# EncoderArm.net
KiCad netlist of a schematic drawn in Altium Designer
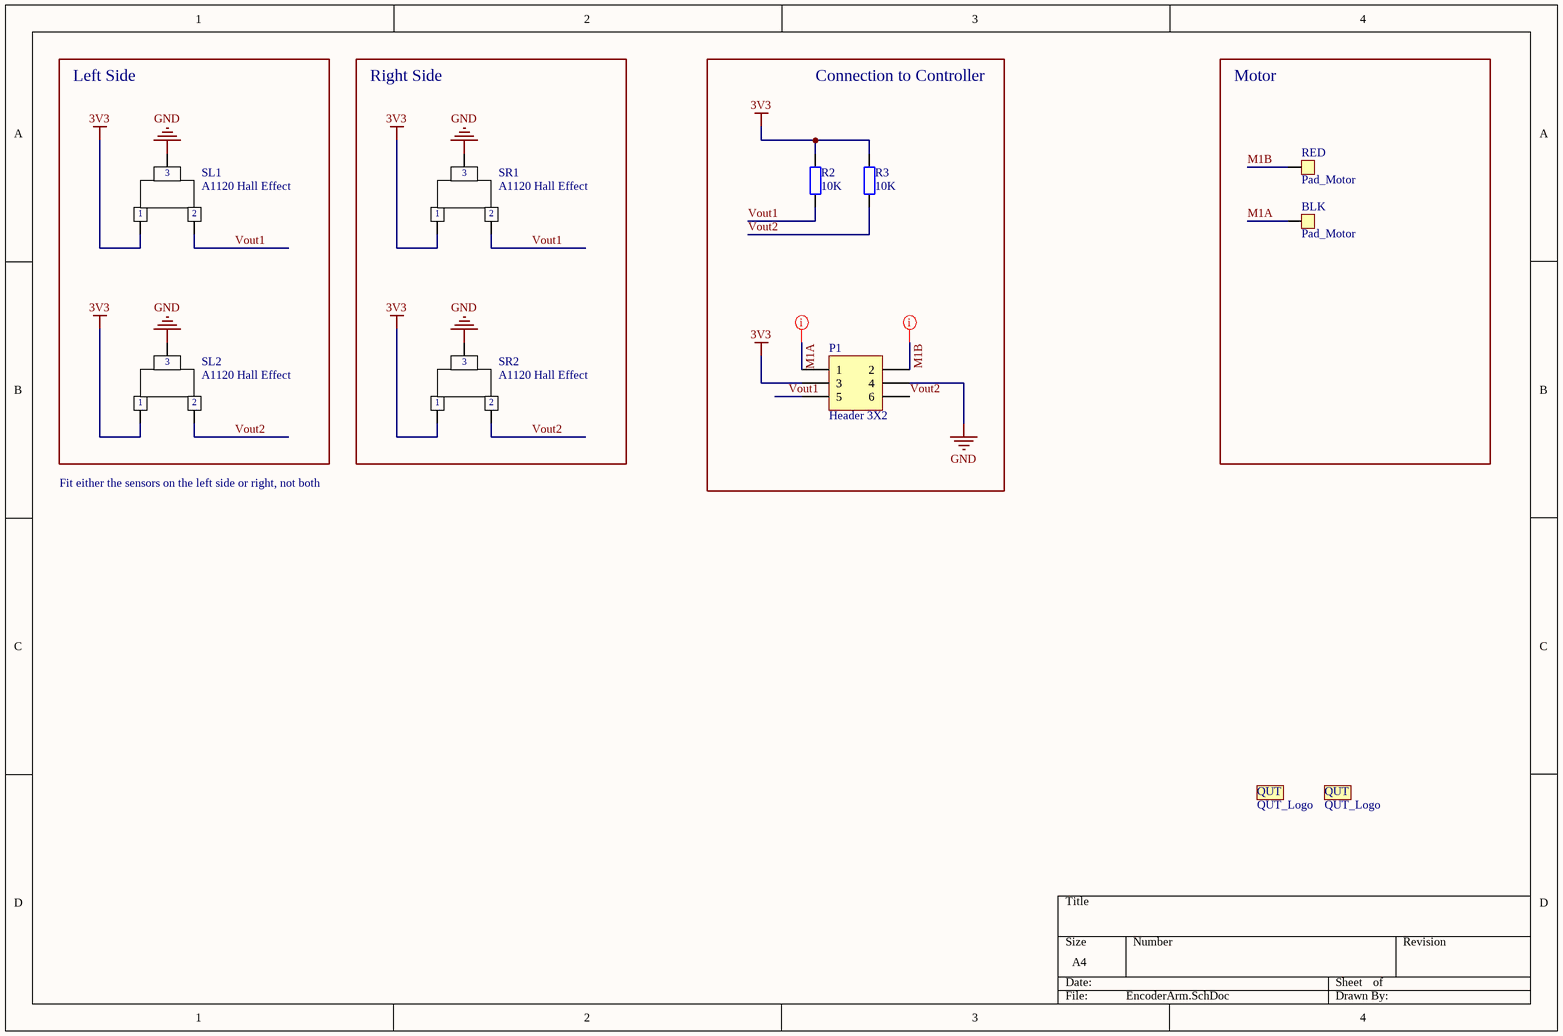
[diagram p0: EncoderArm.SchDoc]

(export (version "E")
  (design (tool "Eeschema 10.0.6"))
  (components
    (comp (ref "BLK")
      (value "Pad_Motor")
      (footprint "Pads_Motor")
      (libsource (lib "PenguinPi_v2") (part "Pad_Motor"))
    )
    (comp (ref "LG1") (value "QUT_Logo") (footprint "QUT_Logo") (libsource (lib "Penguin") (part "QUT_Logo")))
    (comp (ref "LG2") (value "QUT_Logo") (footprint "QUT_Logo") (libsource (lib "Penguin") (part "QUT_Logo")))
    (comp (ref "P1")
      (value "Header 3X2")
      (footprint "HDR2X3")
      (description "Header, 3-Pin, Dual row")
      (fields (field (name "PUBLISHER") "Altium Limited"))
      (libsource (lib "Miscellaneous Connectors") (part "Header 3X2"))
    )
    (comp (ref "R2")
      (value "10K")
      (footprint "6-0805_M")
      (description "Resistor")
      (fields (field (name "Comment") "Res2") (field (name "PUBLISHER") "Altium Limited"))
      (libsource (lib "Miscellaneous Devices") (part "Res2"))
    )
    (comp (ref "R3")
      (value "10K")
      (footprint "6-0805_M")
      (description "Resistor")
      (fields (field (name "Comment") "Res2") (field (name "PUBLISHER") "Altium Limited"))
      (libsource (lib "Miscellaneous Devices") (part "Res2"))
    )
    (comp (ref "RED")
      (value "Pad_Motor")
      (footprint "Pads_Motor")
      (libsource (lib "PenguinPi_v2") (part "Pad_Motor"))
    )
    (comp (ref "SL1")
      (value "A1120 Hall Effect")
      (footprint "SOT23-3N")
      (libsource (lib "QUT") (part "FT_SOT23-3"))
    )
    (comp (ref "SL2")
      (value "A1120 Hall Effect")
      (footprint "SOT23-3N")
      (libsource (lib "QUT") (part "FT_SOT23-3"))
    )
    (comp (ref "SR1")
      (value "A1120 Hall Effect")
      (footprint "SOT23-3N")
      (libsource (lib "QUT") (part "FT_SOT23-3"))
    )
    (comp (ref "SR2")
      (value "A1120 Hall Effect")
      (footprint "SOT23-3N")
      (libsource (lib "QUT") (part "FT_SOT23-3"))
    )
  )
  (nets
    (net (code "1") (name "/M1A") (class "Default")
      (node (ref "BLK") (pin "0") (pinfunction "0_0") (pintype "passive"))
      (node (ref "P1") (pin "1") (pinfunction "1_1") (pintype "passive"))
    )
    (net (code "2") (name "/M1B") (class "Default")
      (node (ref "P1") (pin "2") (pinfunction "2_2") (pintype "passive"))
      (node (ref "RED") (pin "0") (pinfunction "0_0") (pintype "passive"))
    )
    (net (code "3") (name "/Vout1") (class "Default")
      (node (ref "P1") (pin "5") (pinfunction "5_5") (pintype "passive"))
      (node (ref "R2") (pin "1") (pinfunction "1_1") (pintype "passive"))
      (node (ref "SL1") (pin "2") (pinfunction "2_2") (pintype "passive"))
      (node (ref "SR1") (pin "2") (pinfunction "2_2") (pintype "passive"))
    )
    (net (code "4") (name "/Vout2") (class "Default")
      (node (ref "P1") (pin "6") (pinfunction "6_6") (pintype "passive"))
      (node (ref "R3") (pin "1") (pinfunction "1_1") (pintype "passive"))
      (node (ref "SL2") (pin "2") (pinfunction "2_2") (pintype "passive"))
      (node (ref "SR2") (pin "2") (pinfunction "2_2") (pintype "passive"))
    )
    (net (code "5") (name "3V3") (class "Default")
      (node (ref "P1") (pin "3") (pinfunction "3_3") (pintype "passive"))
      (node (ref "R2") (pin "2") (pinfunction "2_2") (pintype "passive"))
      (node (ref "R3") (pin "2") (pinfunction "2_2") (pintype "passive"))
      (node (ref "SL1") (pin "1") (pinfunction "1_1") (pintype "passive"))
      (node (ref "SL2") (pin "1") (pinfunction "1_1") (pintype "passive"))
      (node (ref "SR1") (pin "1") (pinfunction "1_1") (pintype "passive"))
      (node (ref "SR2") (pin "1") (pinfunction "1_1") (pintype "passive"))
    )
    (net (code "6") (name "GND") (class "Default")
      (node (ref "P1") (pin "4") (pinfunction "4_4") (pintype "passive"))
      (node (ref "SL1") (pin "3") (pinfunction "3_3") (pintype "passive"))
      (node (ref "SL2") (pin "3") (pinfunction "3_3") (pintype "passive"))
      (node (ref "SR1") (pin "3") (pinfunction "3_3") (pintype "passive"))
      (node (ref "SR2") (pin "3") (pinfunction "3_3") (pintype "passive"))
    )
  )
)
